# DCC-headlight-V1.net
KiCad netlist of a schematic drawn in EAGLE
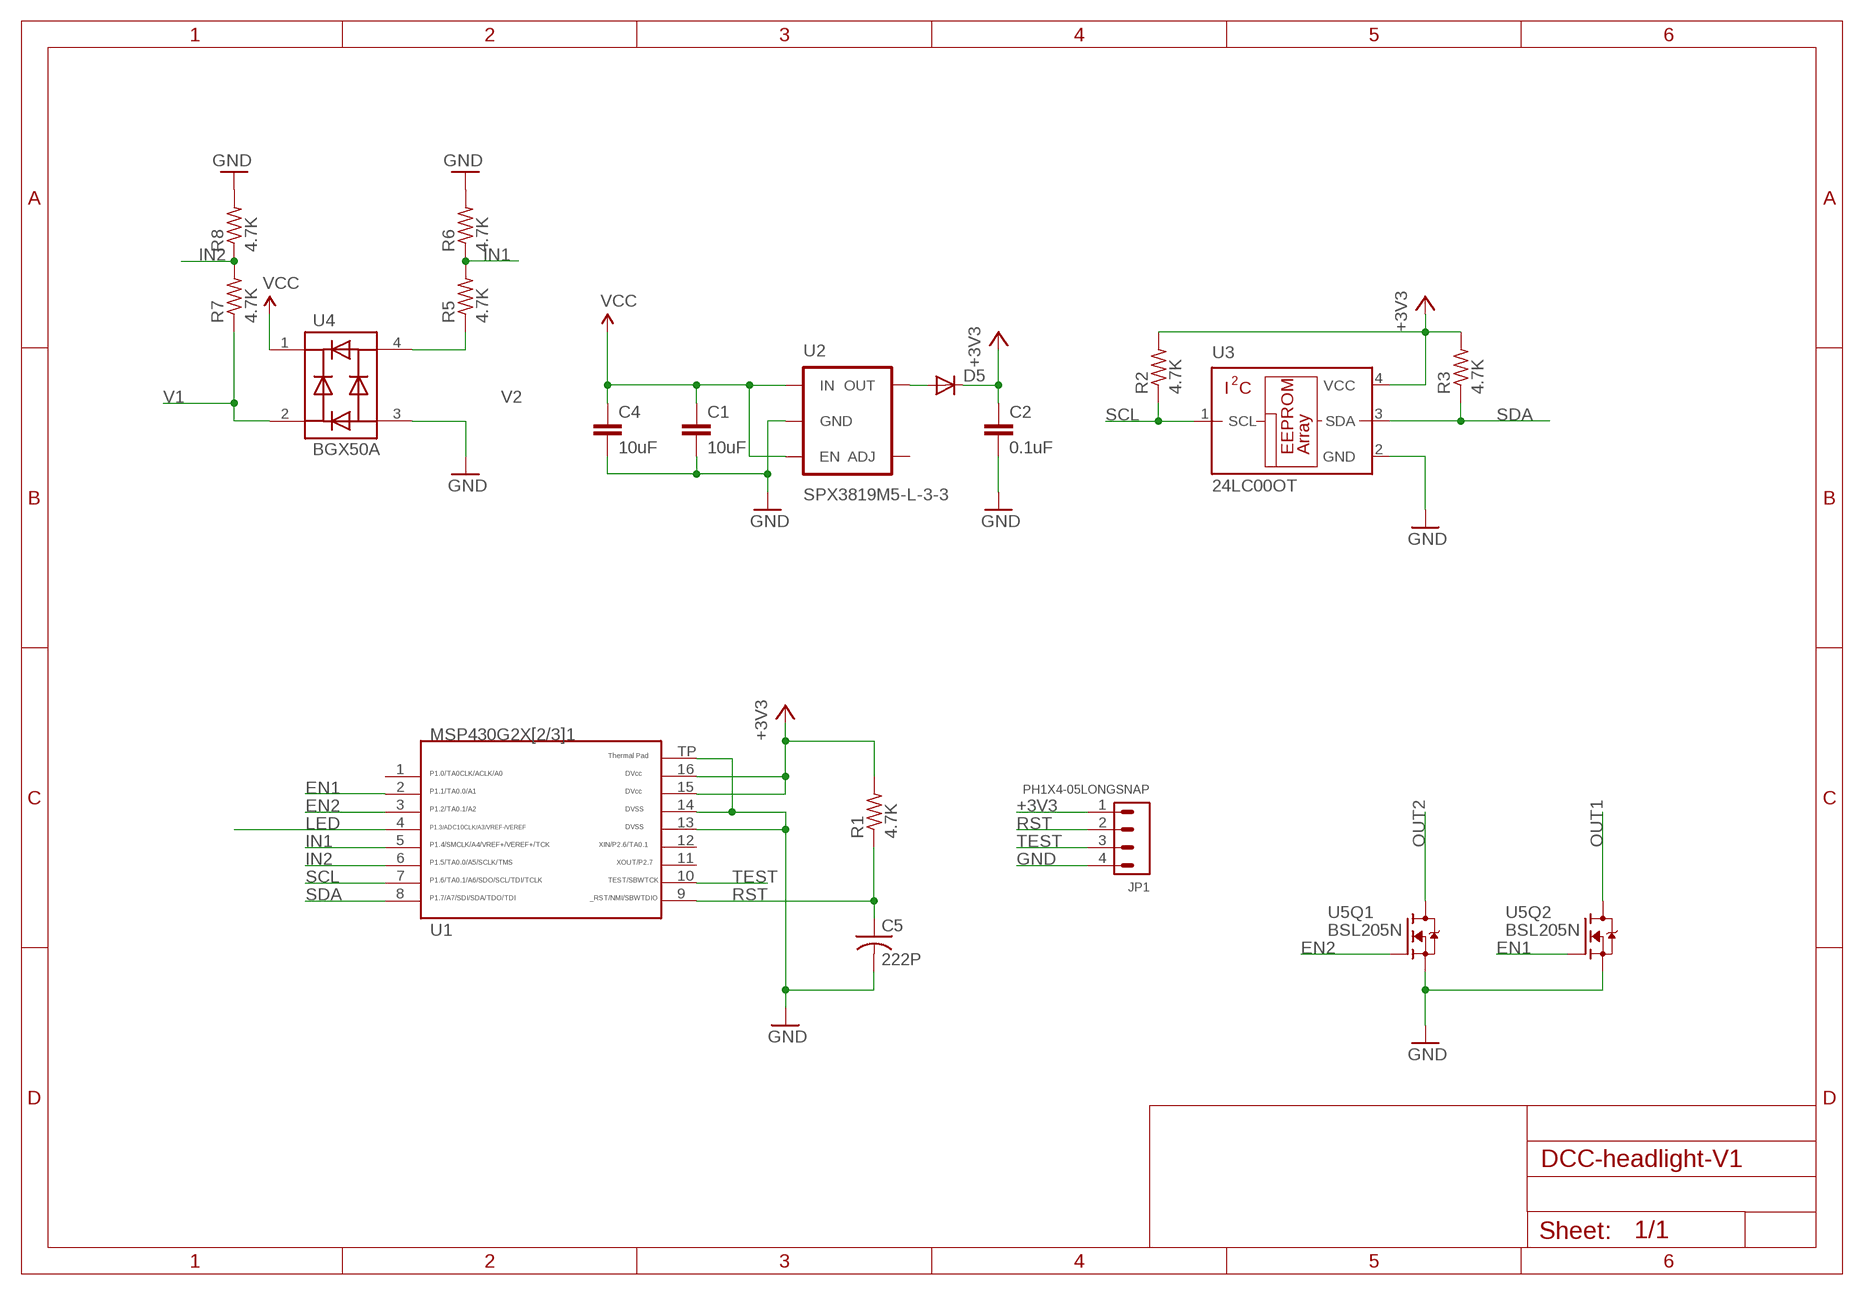
[diagram p0: schematic, sheet 1]

(export (version "E")
  (design (tool "Eeschema 10.0.6"))
  (components
    (comp (ref "C1")
      (value "10uF")
      (footprint "eagle-import:0402-CAP")
      (libsource (lib "eagle-import") (part "CAP0402-CAP"))
    )
    (comp (ref "C2")
      (value "0.1uF")
      (footprint "eagle-import:0402-CAP")
      (libsource (lib "eagle-import") (part "CAP0402-CAP"))
    )
    (comp (ref "C4")
      (value "10uF")
      (footprint "eagle-import:0402-CAP")
      (libsource (lib "eagle-import") (part "CAP0402-CAP"))
    )
    (comp (ref "C5")
      (value "222P")
      (footprint "eagle-import:C0402")
      (libsource (lib "eagle-import") (part "C-USC0402"))
    )
    (comp (ref "D5")
      (value "DIODE-SOD523")
      (footprint "eagle-import:SOD523")
      (libsource (lib "eagle-import") (part "DIODE-SOD523"))
    )
    (comp (ref "JP1")
      (value "PH1X4-05LONGSNAP")
      (footprint "eagle-import:PHLS005-1-4")
      (libsource (lib "eagle-import") (part "PH1X4-05LONGSNAP"))
    )
    (comp (ref "R1")
      (value "4.7K")
      (footprint "eagle-import:R0402")
      (libsource (lib "eagle-import") (part "R-US_R0402"))
    )
    (comp (ref "R2")
      (value "4.7K")
      (footprint "eagle-import:R0402")
      (libsource (lib "eagle-import") (part "R-US_R0402"))
    )
    (comp (ref "R3")
      (value "4.7K")
      (footprint "eagle-import:R0402")
      (libsource (lib "eagle-import") (part "R-US_R0402"))
    )
    (comp (ref "R5")
      (value "4.7K")
      (footprint "eagle-import:R0402")
      (libsource (lib "eagle-import") (part "R-US_R0402"))
    )
    (comp (ref "R6")
      (value "4.7K")
      (footprint "eagle-import:R0402")
      (libsource (lib "eagle-import") (part "R-US_R0402"))
    )
    (comp (ref "R7")
      (value "4.7K")
      (footprint "eagle-import:R0402")
      (libsource (lib "eagle-import") (part "R-US_R0402"))
    )
    (comp (ref "R8")
      (value "4.7K")
      (footprint "eagle-import:R0402")
      (libsource (lib "eagle-import") (part "R-US_R0402"))
    )
    (comp (ref "U1")
      (value "G2X[2/3]1---RSA16")
      (footprint "eagle-import:RSA16")
      (libsource (lib "eagle-import") (part "G2X[2/3]1---RSA16"))
    )
    (comp (ref "U2")
      (value "SPX3819M5-L-3-3")
      (footprint "eagle-import:SOT23-5")
      (libsource (lib "eagle-import") (part "AP2202-ADJ"))
    )
    (comp (ref "U3")
      (value "24LC00OT")
      (footprint "eagle-import:SOT23-5L")
      (fields (field (name "MF") "MICROCHIP") (field (name "MPN") "24LC00T-I/OT"))
      (libsource (lib "eagle-import") (part "2400OTLC"))
    )
    (comp (ref "U4")
      (value "BGX50A")
      (footprint "eagle-import:SOT143")
      (libsource (lib "eagle-import") (part "BGX50A"))
    )
    (comp (ref "U5")
      (value "BSL205N")
      (footprint "eagle-import:SOT23-6")
      (libsource (lib "eagle-import") (part "BSL205N"))
    )
  )
  (nets
    (net (code "1") (name "+3V3") (class "Default")
      (node (ref "C2") (pin "1") (pinfunction "1_1") (pintype "passive"))
      (node (ref "D5") (pin "C") (pinfunction "C_C") (pintype "passive"))
      (node (ref "JP1") (pin "1") (pinfunction "1_1") (pintype "bidirectional"))
      (node (ref "R1") (pin "2") (pinfunction "2_2") (pintype "passive"))
      (node (ref "R2") (pin "2") (pinfunction "2_2") (pintype "passive"))
      (node (ref "R3") (pin "2") (pinfunction "2_2") (pintype "passive"))
      (node (ref "U1") (pin "15") (pinfunction "15_15") (pintype "bidirectional"))
      (node (ref "U1") (pin "16") (pinfunction "16_16") (pintype "bidirectional"))
      (node (ref "U3") (pin "4") (pinfunction "VCC_4") (pintype "power_in"))
    )
    (net (code "2") (name "/EN1") (class "Default")
      (node (ref "U1") (pin "2") (pinfunction "2_2") (pintype "bidirectional"))
      (node (ref "U5") (pin "3") (pinfunction "G_3") (pintype "passive"))
    )
    (net (code "3") (name "/EN2") (class "Default")
      (node (ref "U1") (pin "3") (pinfunction "3_3") (pintype "bidirectional"))
      (node (ref "U5") (pin "1") (pinfunction "G_1") (pintype "passive"))
    )
    (net (code "4") (name "/IN1") (class "Default")
      (node (ref "R5") (pin "2") (pinfunction "2_2") (pintype "passive"))
      (node (ref "R6") (pin "1") (pinfunction "1_1") (pintype "passive"))
      (node (ref "U1") (pin "5") (pinfunction "5_5") (pintype "bidirectional"))
    )
    (net (code "5") (name "/IN2") (class "Default")
      (node (ref "R7") (pin "2") (pinfunction "2_2") (pintype "passive"))
      (node (ref "R8") (pin "1") (pinfunction "1_1") (pintype "passive"))
      (node (ref "U1") (pin "6") (pinfunction "6_6") (pintype "bidirectional"))
    )
    (net (code "6") (name "/LED") (class "Default")
      (node (ref "U1") (pin "4") (pinfunction "4_4") (pintype "bidirectional"))
    )
    (net (code "7") (name "/OUT1") (class "Default")
      (node (ref "U5") (pin "4") (pinfunction "D_4") (pintype "passive"))
    )
    (net (code "8") (name "/OUT2") (class "Default")
      (node (ref "U5") (pin "6") (pinfunction "D_6") (pintype "passive"))
    )
    (net (code "9") (name "/RST") (class "Default")
      (node (ref "C5") (pin "1") (pinfunction "1_1") (pintype "passive"))
      (node (ref "JP1") (pin "2") (pinfunction "2_2") (pintype "bidirectional"))
      (node (ref "R1") (pin "1") (pinfunction "1_1") (pintype "passive"))
      (node (ref "U1") (pin "9") (pinfunction "9_9") (pintype "bidirectional"))
    )
    (net (code "10") (name "/SCL") (class "Default")
      (node (ref "R2") (pin "1") (pinfunction "1_1") (pintype "passive"))
      (node (ref "U1") (pin "7") (pinfunction "7_7") (pintype "bidirectional"))
      (node (ref "U3") (pin "1") (pinfunction "SCL_1") (pintype "input"))
    )
    (net (code "11") (name "/SDA") (class "Default")
      (node (ref "R3") (pin "1") (pinfunction "1_1") (pintype "passive"))
      (node (ref "U1") (pin "8") (pinfunction "8_8") (pintype "bidirectional"))
      (node (ref "U3") (pin "3") (pinfunction "SDA_3") (pintype "bidirectional"))
    )
    (net (code "12") (name "/TEST") (class "Default")
      (node (ref "JP1") (pin "3") (pinfunction "3_3") (pintype "bidirectional"))
      (node (ref "U1") (pin "10") (pinfunction "10_10") (pintype "bidirectional"))
    )
    (net (code "13") (name "/V1") (class "Default")
      (node (ref "R7") (pin "1") (pinfunction "1_1") (pintype "passive"))
      (node (ref "U4") (pin "2") (pinfunction "2_2") (pintype "bidirectional"))
    )
    (net (code "14") (name "/V2") (class "Default")
      (node (ref "R5") (pin "1") (pinfunction "1_1") (pintype "passive"))
      (node (ref "U4") (pin "4") (pinfunction "4_4") (pintype "bidirectional"))
    )
    (net (code "15") (name "GND") (class "Default")
      (node (ref "C1") (pin "2") (pinfunction "2_2") (pintype "passive"))
      (node (ref "C2") (pin "2") (pinfunction "2_2") (pintype "passive"))
      (node (ref "C4") (pin "2") (pinfunction "2_2") (pintype "passive"))
      (node (ref "C5") (pin "2") (pinfunction "2_2") (pintype "passive"))
      (node (ref "JP1") (pin "4") (pinfunction "4_4") (pintype "bidirectional"))
      (node (ref "R6") (pin "2") (pinfunction "2_2") (pintype "passive"))
      (node (ref "R8") (pin "2") (pinfunction "2_2") (pintype "passive"))
      (node (ref "U1") (pin "13") (pinfunction "13_13") (pintype "bidirectional"))
      (node (ref "U1") (pin "14") (pinfunction "14_14") (pintype "bidirectional"))
      (node (ref "U1") (pin "TP") (pinfunction "TP_TP") (pintype "bidirectional"))
      (node (ref "U2") (pin "2") (pinfunction "GND_2") (pintype "input"))
      (node (ref "U3") (pin "2") (pinfunction "GND_2") (pintype "power_in"))
      (node (ref "U4") (pin "3") (pinfunction "3_3") (pintype "bidirectional"))
      (node (ref "U5") (pin "2") (pinfunction "S_2") (pintype "passive"))
      (node (ref "U5") (pin "5") (pinfunction "S_5") (pintype "passive"))
    )
    (net (code "16") (name "Net-(U2-OUT)") (class "Default")
      (node (ref "D5") (pin "A") (pinfunction "A_A") (pintype "passive"))
      (node (ref "U2") (pin "5") (pinfunction "OUT_5") (pintype "passive"))
    )
    (net (code "17") (name "VCC") (class "Default")
      (node (ref "C1") (pin "1") (pinfunction "1_1") (pintype "passive"))
      (node (ref "C4") (pin "1") (pinfunction "1_1") (pintype "passive"))
      (node (ref "U2") (pin "1") (pinfunction "IN_1") (pintype "input"))
      (node (ref "U2") (pin "3") (pinfunction "EN_3") (pintype "input"))
      (node (ref "U4") (pin "1") (pinfunction "1_1") (pintype "bidirectional"))
    )
    (net (code "18") (name "unconnected-(U1-Pad1)") (class "Default")
      (node (ref "U1") (pin "1") (pinfunction "1_1") (pintype "bidirectional"))
    )
    (net (code "19") (name "unconnected-(U1-Pad11)") (class "Default")
      (node (ref "U1") (pin "11") (pinfunction "11_11") (pintype "bidirectional"))
    )
    (net (code "20") (name "unconnected-(U1-Pad12)") (class "Default")
      (node (ref "U1") (pin "12") (pinfunction "12_12") (pintype "bidirectional"))
    )
    (net (code "21") (name "unconnected-(U2-ADJ-Pad4)") (class "Default")
      (node (ref "U2") (pin "4") (pinfunction "ADJ_4") (pintype "input"))
    )
  )
)
